# extension_board.net
KiCad netlist of a schematic drawn in EAGLE
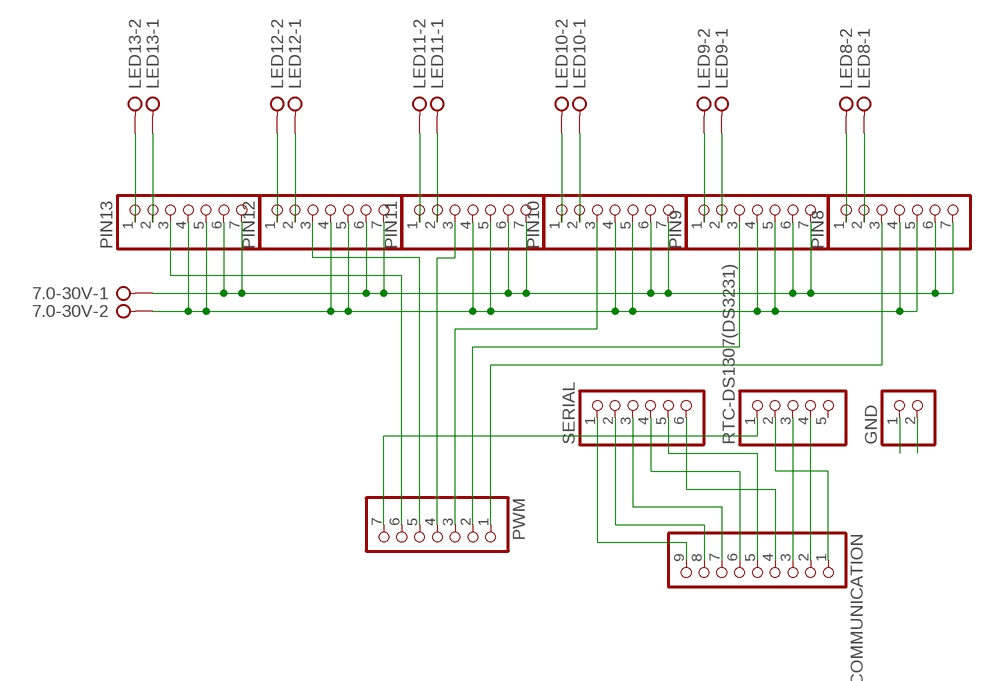
[diagram p0: schematic, sheet 1]

(export (version "E")
  (design (tool "Eeschema 10.0.6"))
  (components
    (comp (ref "7.0-30V")
      (value "W237-02P")
      (footprint "eagle-import:W237-132")
      (libsource (lib "eagle-import") (part "W237-02P"))
    )
    (comp (ref "COMMUNICATION")
      (value "PINHD-1X9")
      (footprint "eagle-import:1X09")
      (libsource (lib "eagle-import") (part "PINHD-1X9"))
    )
    (comp (ref "GND")
      (value "PINHD-1X2")
      (footprint "eagle-import:1X02")
      (libsource (lib "eagle-import") (part "PINHD-1X2"))
    )
    (comp (ref "LED8")
      (value "W237-02P")
      (footprint "eagle-import:W237-132")
      (libsource (lib "eagle-import") (part "W237-02P"))
    )
    (comp (ref "LED9")
      (value "W237-02P")
      (footprint "eagle-import:W237-132")
      (libsource (lib "eagle-import") (part "W237-02P"))
    )
    (comp (ref "LED10")
      (value "W237-02P")
      (footprint "eagle-import:W237-132")
      (libsource (lib "eagle-import") (part "W237-02P"))
    )
    (comp (ref "LED11")
      (value "W237-02P")
      (footprint "eagle-import:W237-132")
      (libsource (lib "eagle-import") (part "W237-02P"))
    )
    (comp (ref "LED12")
      (value "W237-02P")
      (footprint "eagle-import:W237-132")
      (libsource (lib "eagle-import") (part "W237-02P"))
    )
    (comp (ref "LED13")
      (value "W237-02P")
      (footprint "eagle-import:W237-132")
      (libsource (lib "eagle-import") (part "W237-02P"))
    )
    (comp (ref "PIN8")
      (value "PINHD-1X7")
      (footprint "eagle-import:1X07")
      (libsource (lib "eagle-import") (part "PINHD-1X7"))
    )
    (comp (ref "PIN9")
      (value "PINHD-1X7")
      (footprint "eagle-import:1X07")
      (libsource (lib "eagle-import") (part "PINHD-1X7"))
    )
    (comp (ref "PIN10")
      (value "PINHD-1X7")
      (footprint "eagle-import:1X07")
      (libsource (lib "eagle-import") (part "PINHD-1X7"))
    )
    (comp (ref "PIN11")
      (value "PINHD-1X7")
      (footprint "eagle-import:1X07")
      (libsource (lib "eagle-import") (part "PINHD-1X7"))
    )
    (comp (ref "PIN12")
      (value "PINHD-1X7")
      (footprint "eagle-import:1X07")
      (libsource (lib "eagle-import") (part "PINHD-1X7"))
    )
    (comp (ref "PIN13")
      (value "PINHD-1X7")
      (footprint "eagle-import:1X07")
      (libsource (lib "eagle-import") (part "PINHD-1X7"))
    )
    (comp (ref "PWM")
      (value "PINHD-1X7")
      (footprint "eagle-import:1X07")
      (libsource (lib "eagle-import") (part "PINHD-1X7"))
    )
    (comp (ref "RTC-DS1307(DS3231)")
      (value "PINHD-1X5")
      (footprint "eagle-import:1X05")
      (libsource (lib "eagle-import") (part "PINHD-1X5"))
    )
    (comp (ref "SERIAL")
      (value "PINHD-1X6")
      (footprint "eagle-import:1X06")
      (libsource (lib "eagle-import") (part "PINHD-1X6"))
    )
  )
  (nets
    (net (code "1") (name "/GND") (class "Default")
      (node (ref "7.0-30V") (pin "2") (pinfunction "KL_2") (pintype "passive"))
      (node (ref "GND") (pin "1") (pinfunction "1_1") (pintype "passive"))
      (node (ref "PIN10") (pin "4") (pinfunction "4_4") (pintype "passive"))
      (node (ref "PIN10") (pin "5") (pinfunction "5_5") (pintype "passive"))
      (node (ref "PIN11") (pin "4") (pinfunction "4_4") (pintype "passive"))
      (node (ref "PIN11") (pin "5") (pinfunction "5_5") (pintype "passive"))
      (node (ref "PIN12") (pin "4") (pinfunction "4_4") (pintype "passive"))
      (node (ref "PIN12") (pin "5") (pinfunction "5_5") (pintype "passive"))
      (node (ref "PIN13") (pin "4") (pinfunction "4_4") (pintype "passive"))
      (node (ref "PIN13") (pin "5") (pinfunction "5_5") (pintype "passive"))
      (node (ref "PIN8") (pin "4") (pinfunction "4_4") (pintype "passive"))
      (node (ref "PIN8") (pin "5") (pinfunction "5_5") (pintype "passive"))
      (node (ref "PIN9") (pin "4") (pinfunction "4_4") (pintype "passive"))
      (node (ref "PIN9") (pin "5") (pinfunction "5_5") (pintype "passive"))
      (node (ref "PWM") (pin "7") (pinfunction "7_7") (pintype "passive"))
      (node (ref "RTC-DS1307(DS3231)") (pin "1") (pinfunction "1_1") (pintype "passive"))
    )
    (net (code "2") (name "/VCC") (class "Default")
      (node (ref "COMMUNICATION") (pin "1") (pinfunction "1_1") (pintype "passive"))
      (node (ref "GND") (pin "2") (pinfunction "2_2") (pintype "passive"))
      (node (ref "RTC-DS1307(DS3231)") (pin "2") (pinfunction "2_2") (pintype "passive"))
    )
    (net (code "3") (name "Net-(7.0-30VA-KL)") (class "Default")
      (node (ref "7.0-30V") (pin "1") (pinfunction "KL_1") (pintype "passive"))
      (node (ref "PIN10") (pin "6") (pinfunction "6_6") (pintype "passive"))
      (node (ref "PIN10") (pin "7") (pinfunction "7_7") (pintype "passive"))
      (node (ref "PIN11") (pin "6") (pinfunction "6_6") (pintype "passive"))
      (node (ref "PIN11") (pin "7") (pinfunction "7_7") (pintype "passive"))
      (node (ref "PIN12") (pin "6") (pinfunction "6_6") (pintype "passive"))
      (node (ref "PIN12") (pin "7") (pinfunction "7_7") (pintype "passive"))
      (node (ref "PIN13") (pin "6") (pinfunction "6_6") (pintype "passive"))
      (node (ref "PIN13") (pin "7") (pinfunction "7_7") (pintype "passive"))
      (node (ref "PIN8") (pin "6") (pinfunction "6_6") (pintype "passive"))
      (node (ref "PIN8") (pin "7") (pinfunction "7_7") (pintype "passive"))
      (node (ref "PIN9") (pin "6") (pinfunction "6_6") (pintype "passive"))
      (node (ref "PIN9") (pin "7") (pinfunction "7_7") (pintype "passive"))
    )
    (net (code "4") (name "Net-(COMMUNICATION-Pad2)") (class "Default")
      (node (ref "COMMUNICATION") (pin "2") (pinfunction "2_2") (pintype "passive"))
      (node (ref "RTC-DS1307(DS3231)") (pin "4") (pinfunction "4_4") (pintype "passive"))
    )
    (net (code "5") (name "Net-(COMMUNICATION-Pad3)") (class "Default")
      (node (ref "COMMUNICATION") (pin "3") (pinfunction "3_3") (pintype "passive"))
      (node (ref "RTC-DS1307(DS3231)") (pin "3") (pinfunction "3_3") (pintype "passive"))
    )
    (net (code "6") (name "Net-(COMMUNICATION-Pad4)") (class "Default")
      (node (ref "COMMUNICATION") (pin "4") (pinfunction "4_4") (pintype "passive"))
      (node (ref "SERIAL") (pin "6") (pinfunction "6_6") (pintype "passive"))
    )
    (net (code "7") (name "Net-(COMMUNICATION-Pad5)") (class "Default")
      (node (ref "COMMUNICATION") (pin "5") (pinfunction "5_5") (pintype "passive"))
      (node (ref "SERIAL") (pin "5") (pinfunction "5_5") (pintype "passive"))
    )
    (net (code "8") (name "Net-(COMMUNICATION-Pad6)") (class "Default")
      (node (ref "COMMUNICATION") (pin "6") (pinfunction "6_6") (pintype "passive"))
      (node (ref "SERIAL") (pin "4") (pinfunction "4_4") (pintype "passive"))
    )
    (net (code "9") (name "Net-(COMMUNICATION-Pad7)") (class "Default")
      (node (ref "COMMUNICATION") (pin "7") (pinfunction "7_7") (pintype "passive"))
      (node (ref "SERIAL") (pin "3") (pinfunction "3_3") (pintype "passive"))
    )
    (net (code "10") (name "Net-(COMMUNICATION-Pad8)") (class "Default")
      (node (ref "COMMUNICATION") (pin "8") (pinfunction "8_8") (pintype "passive"))
      (node (ref "SERIAL") (pin "2") (pinfunction "2_2") (pintype "passive"))
    )
    (net (code "11") (name "Net-(COMMUNICATION-Pad9)") (class "Default")
      (node (ref "COMMUNICATION") (pin "9") (pinfunction "9_9") (pintype "passive"))
      (node (ref "SERIAL") (pin "1") (pinfunction "1_1") (pintype "passive"))
    )
    (net (code "12") (name "Net-(LED8A-KL)") (class "Default")
      (node (ref "LED8") (pin "1") (pinfunction "KL_1") (pintype "passive"))
      (node (ref "PIN8") (pin "2") (pinfunction "2_2") (pintype "passive"))
    )
    (net (code "13") (name "Net-(LED8B-KL)") (class "Default")
      (node (ref "LED8") (pin "2") (pinfunction "KL_2") (pintype "passive"))
      (node (ref "PIN8") (pin "1") (pinfunction "1_1") (pintype "passive"))
    )
    (net (code "14") (name "Net-(LED9A-KL)") (class "Default")
      (node (ref "LED9") (pin "1") (pinfunction "KL_1") (pintype "passive"))
      (node (ref "PIN9") (pin "2") (pinfunction "2_2") (pintype "passive"))
    )
    (net (code "15") (name "Net-(LED9B-KL)") (class "Default")
      (node (ref "LED9") (pin "2") (pinfunction "KL_2") (pintype "passive"))
      (node (ref "PIN9") (pin "1") (pinfunction "1_1") (pintype "passive"))
    )
    (net (code "16") (name "Net-(LED10A-KL)") (class "Default")
      (node (ref "LED10") (pin "1") (pinfunction "KL_1") (pintype "passive"))
      (node (ref "PIN10") (pin "2") (pinfunction "2_2") (pintype "passive"))
    )
    (net (code "17") (name "Net-(LED10B-KL)") (class "Default")
      (node (ref "LED10") (pin "2") (pinfunction "KL_2") (pintype "passive"))
      (node (ref "PIN10") (pin "1") (pinfunction "1_1") (pintype "passive"))
    )
    (net (code "18") (name "Net-(LED11A-KL)") (class "Default")
      (node (ref "LED11") (pin "1") (pinfunction "KL_1") (pintype "passive"))
      (node (ref "PIN11") (pin "2") (pinfunction "2_2") (pintype "passive"))
    )
    (net (code "19") (name "Net-(LED11B-KL)") (class "Default")
      (node (ref "LED11") (pin "2") (pinfunction "KL_2") (pintype "passive"))
      (node (ref "PIN11") (pin "1") (pinfunction "1_1") (pintype "passive"))
    )
    (net (code "20") (name "Net-(LED12A-KL)") (class "Default")
      (node (ref "LED12") (pin "1") (pinfunction "KL_1") (pintype "passive"))
      (node (ref "PIN12") (pin "2") (pinfunction "2_2") (pintype "passive"))
    )
    (net (code "21") (name "Net-(LED12B-KL)") (class "Default")
      (node (ref "LED12") (pin "2") (pinfunction "KL_2") (pintype "passive"))
      (node (ref "PIN12") (pin "1") (pinfunction "1_1") (pintype "passive"))
    )
    (net (code "22") (name "Net-(LED13A-KL)") (class "Default")
      (node (ref "LED13") (pin "1") (pinfunction "KL_1") (pintype "passive"))
      (node (ref "PIN13") (pin "2") (pinfunction "2_2") (pintype "passive"))
    )
    (net (code "23") (name "Net-(LED13B-KL)") (class "Default")
      (node (ref "LED13") (pin "2") (pinfunction "KL_2") (pintype "passive"))
      (node (ref "PIN13") (pin "1") (pinfunction "1_1") (pintype "passive"))
    )
    (net (code "24") (name "Net-(PIN8-Pad3)") (class "Default")
      (node (ref "PIN8") (pin "3") (pinfunction "3_3") (pintype "passive"))
      (node (ref "PWM") (pin "1") (pinfunction "1_1") (pintype "passive"))
    )
    (net (code "25") (name "Net-(PIN9-Pad3)") (class "Default")
      (node (ref "PIN9") (pin "3") (pinfunction "3_3") (pintype "passive"))
      (node (ref "PWM") (pin "2") (pinfunction "2_2") (pintype "passive"))
    )
    (net (code "26") (name "Net-(PIN10-Pad3)") (class "Default")
      (node (ref "PIN10") (pin "3") (pinfunction "3_3") (pintype "passive"))
      (node (ref "PWM") (pin "3") (pinfunction "3_3") (pintype "passive"))
    )
    (net (code "27") (name "Net-(PIN11-Pad3)") (class "Default")
      (node (ref "PIN11") (pin "3") (pinfunction "3_3") (pintype "passive"))
      (node (ref "PWM") (pin "4") (pinfunction "4_4") (pintype "passive"))
    )
    (net (code "28") (name "Net-(PIN12-Pad3)") (class "Default")
      (node (ref "PIN12") (pin "3") (pinfunction "3_3") (pintype "passive"))
      (node (ref "PWM") (pin "5") (pinfunction "5_5") (pintype "passive"))
    )
    (net (code "29") (name "Net-(PIN13-Pad3)") (class "Default")
      (node (ref "PIN13") (pin "3") (pinfunction "3_3") (pintype "passive"))
      (node (ref "PWM") (pin "6") (pinfunction "6_6") (pintype "passive"))
    )
    (net (code "30") (name "unconnected-(RTC-DS1307(DS3231)-Pad5)") (class "Default")
      (node (ref "RTC-DS1307(DS3231)") (pin "5") (pinfunction "5_5") (pintype "passive"))
    )
  )
)
